# ST_LINK_V2-1.net
KiCad netlist of a schematic drawn in Altium Designer
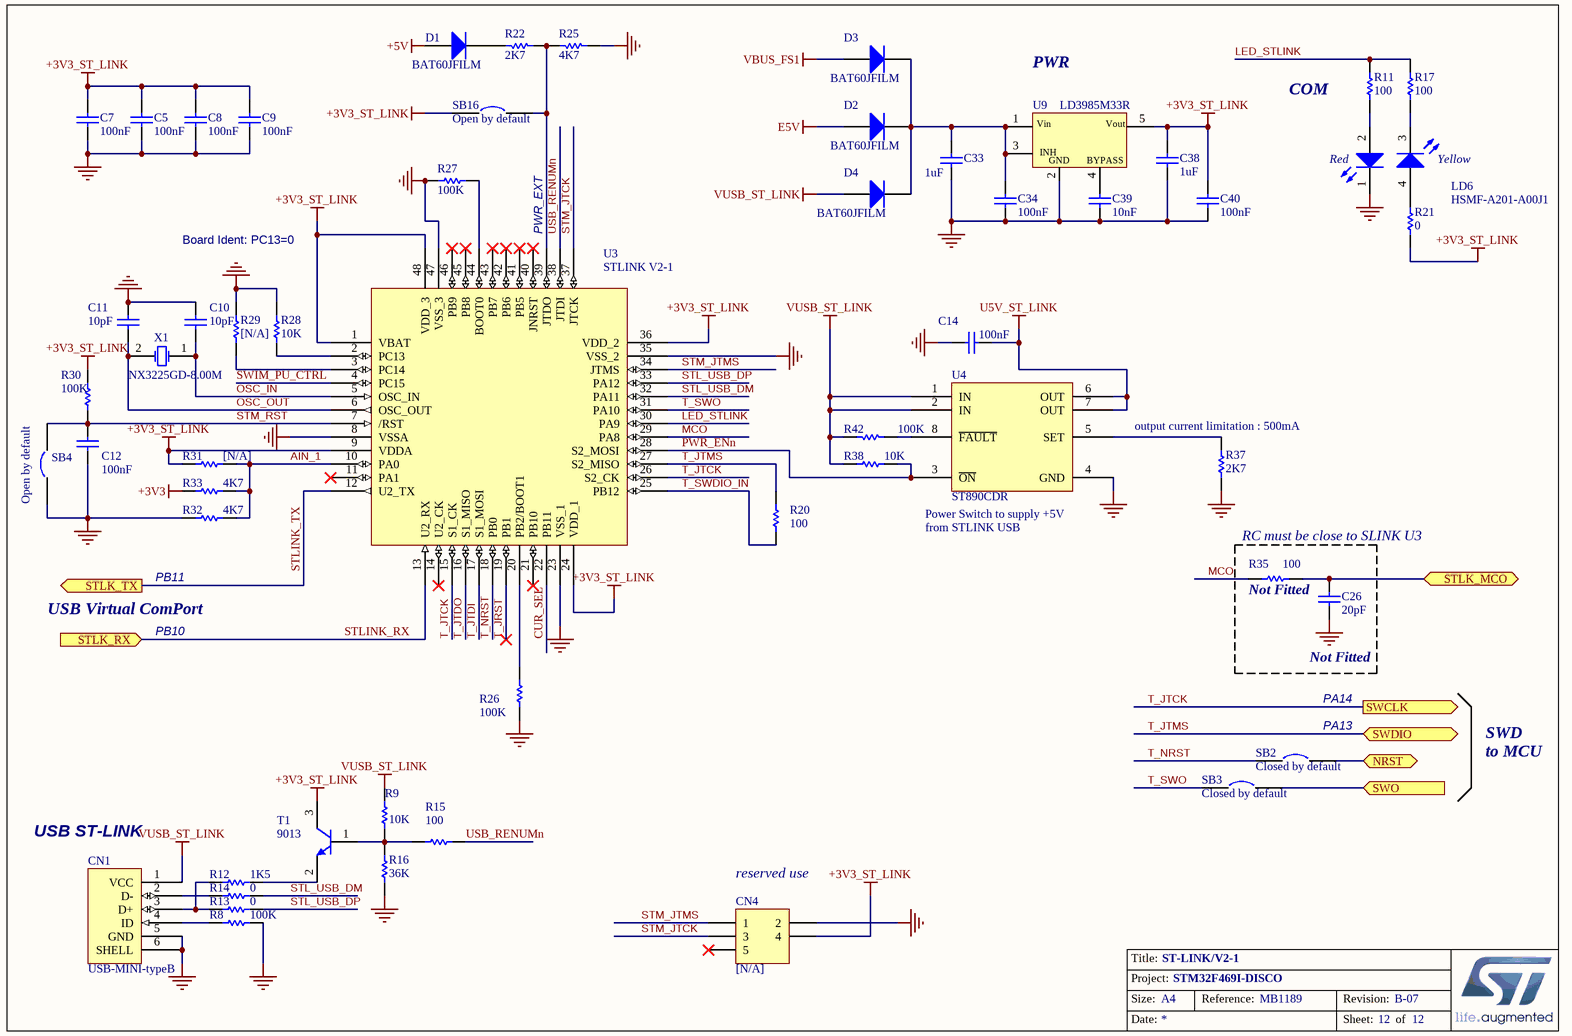
[diagram p0: ST_LINK_V2-1.SCHDOC]

(export (version "E")
  (design (tool "Eeschema 10.0.6"))
  (components
    (comp (ref "C5")
      (value "100nF")
      (footprint "0402C")
      (description "Capacitor 0402 / 0603 / 0805")
      (libsource (lib "MCD_TOOLS") (part "Capacitor_ST"))
    )
    (comp (ref "C7")
      (value "100nF")
      (footprint "0402C")
      (description "Capacitor 0402 / 0603 / 0805")
      (libsource (lib "MCD_TOOLS") (part "Capacitor_ST"))
    )
    (comp (ref "C8")
      (value "100nF")
      (footprint "0402C")
      (description "Capacitor 0402 / 0603 / 0805")
      (libsource (lib "MCD_TOOLS") (part "Capacitor_ST"))
    )
    (comp (ref "C9")
      (value "100nF")
      (footprint "0402C")
      (description "Capacitor 0402 / 0603 / 0805")
      (libsource (lib "MCD_TOOLS") (part "Capacitor_ST"))
    )
    (comp (ref "C10")
      (value "10pF")
      (footprint "0603C")
      (description "Capacitor 0402 / 0603 / 0805")
      (libsource (lib "MCD_TOOLS") (part "Capacitor_ST"))
    )
    (comp (ref "C11")
      (value "10pF")
      (footprint "0603C")
      (description "Capacitor 0402 / 0603 / 0805")
      (libsource (lib "MCD_TOOLS") (part "Capacitor_ST"))
    )
    (comp (ref "C12")
      (value "100nF")
      (footprint "0402C")
      (description "Capacitor 0402 / 0603 / 0805")
      (libsource (lib "MCD_TOOLS") (part "Capacitor_ST"))
    )
    (comp (ref "C14")
      (value "100nF")
      (footprint "0402C")
      (description "Capacitor 0402 / 0603 / 0805")
      (libsource (lib "MCD_TOOLS") (part "Capacitor_ST"))
    )
    (comp (ref "C26")
      (value "20pF")
      (footprint "0603C")
      (description "Capacitor,20pF,50V,NPO,5%,0402,YAGEO")
      (libsource (lib "MCD_TOOLS") (part "Cap_20pF_NPO_5%_0402"))
    )
    (comp (ref "C33")
      (value "1uF")
      (footprint "0603C")
      (description "Capacitor")
      (fields (field (name "TOLERANCE") "10%"))
      (libsource (lib "MB963_1") (part "CAP SMD 0603  X5R 1µF 25V 10%"))
    )
    (comp (ref "C34")
      (value "100nF")
      (footprint "0402C")
      (description "Capacitor 0402 / 0603 / 0805")
      (libsource (lib "MCD_TOOLS") (part "Capacitor_ST"))
    )
    (comp (ref "C38")
      (value "1uF")
      (footprint "0603C")
      (description "Capacitor")
      (fields (field (name "TOLERANCE") "10%"))
      (libsource (lib "MB963_1") (part "CAP SMD 0603  X5R 1µF 25V 10%"))
    )
    (comp (ref "C39")
      (value "10nF")
      (footprint "0603C")
      (description "0603  X7R 10NF")
      (fields (field (name "TOLERANCE") "10%"))
      (libsource (lib "MB963_1") (part "CAP SMD 0603  X7R 10000PF 50V 10%"))
    )
    (comp (ref "C40")
      (value "100nF")
      (footprint "0402C")
      (description "Capacitor 0402 / 0603 / 0805")
      (libsource (lib "MCD_TOOLS") (part "Capacitor_ST"))
    )
    (comp (ref "CN1")
      (value "USB-MINI-typeB")
      (footprint "MINIUSB_AB_5SM_RA")
      (description "USB,MINI-USB-5P/F, 5075BMR-05-M")
      (libsource (lib "MCD_TOOLS") (part "USB-MINI-typeB connector"))
    )
    (comp (ref "CN4")
      (value "[N/A]")
      (footprint "HDR_2X3-1_2R54-6")
      (description "Header, 3-Pin, Dual row")
      (fields (field (name "PUBLISHER") "Altium Limited"))
      (libsource (lib "Miscellaneous Connectors") (part "Header 3X2"))
    )
    (comp (ref "D1")
      (value "BAT60JFILM")
      (footprint "SOD-323")
      (libsource (lib "MCD_TOOLS") (part "BAT60JFILM"))
    )
    (comp (ref "D2")
      (value "BAT60JFILM")
      (footprint "SOD-323")
      (libsource (lib "MCD_TOOLS") (part "BAT60JFILM"))
    )
    (comp (ref "D3")
      (value "BAT60JFILM")
      (footprint "SOD-323")
      (libsource (lib "MCD_TOOLS") (part "BAT60JFILM"))
    )
    (comp (ref "D4")
      (value "BAT60JFILM")
      (footprint "SOD-323")
      (libsource (lib "MCD_TOOLS") (part "BAT60JFILM"))
    )
    (comp (ref "LD6")
      (value "HSMF-A201-A00J1")
      (footprint "LED2_3528")
      (libsource (lib "MB819") (part "HSMF-A201-A00J1"))
    )
    (comp (ref "R8")
      (value "100K")
      (footprint "0603R")
      (description "Resistor")
      (fields (field (name "PUBLISHER") "Altium Limited"))
      (libsource (lib "Miscellaneous Devices") (part "res1"))
    )
    (comp (ref "R9")
      (value "10K")
      (footprint "0402R")
      (description "Resistor")
      (fields (field (name "PUBLISHER") "Altium Limited"))
      (libsource (lib "") (part "Res1_2"))
    )
    (comp (ref "R11")
      (value "100")
      (footprint "0603R")
      (description "Resistor")
      (fields (field (name "PUBLISHER") "Altium Limited"))
      (libsource (lib "") (part "Res1_2"))
    )
    (comp (ref "R12")
      (value "1K5")
      (footprint "0603R")
      (description "Resistor 0402 or 0603 or 0805")
      (libsource (lib "Miscellaneous Devices") (part "Res1"))
    )
    (comp (ref "R13")
      (value "0")
      (footprint "0603R")
      (description "Resistor 0402 or 0603 or 0805")
      (libsource (lib "Miscellaneous Devices") (part "Res1"))
    )
    (comp (ref "R14")
      (value "0")
      (footprint "0603R")
      (description "Resistor 0402 or 0603 or 0805")
      (libsource (lib "Miscellaneous Devices") (part "Res1"))
    )
    (comp (ref "R15")
      (value "100")
      (footprint "0603R")
      (description "Resistor 0402 or 0603 or 0805")
      (libsource (lib "Miscellaneous Devices") (part "Res1"))
    )
    (comp (ref "R16")
      (value "36K")
      (footprint "0603R")
      (description "Resistor")
      (fields (field (name "PUBLISHER") "Altium Limited"))
      (libsource (lib "") (part "Res1_2"))
    )
    (comp (ref "R17")
      (value "100")
      (footprint "0603R")
      (description "Resistor")
      (fields (field (name "PUBLISHER") "Altium Limited"))
      (libsource (lib "") (part "Res1_2"))
    )
    (comp (ref "R20")
      (value "100")
      (footprint "STM-SMEE:0603R")
      (description "Resistor 0402 or 0603 or 0805")
      (libsource (lib "MCD_TOOLS") (part "Resistor_ST"))
    )
    (comp (ref "R21")
      (value "0")
      (footprint "0603R")
      (description "Resistor")
      (fields (field (name "PUBLISHER") "Altium Limited"))
      (libsource (lib "") (part "Res1_2"))
    )
    (comp (ref "R22")
      (value "2K7")
      (footprint "0603R")
      (description "Resistor")
      (fields (field (name "PUBLISHER") "Altium Limited"))
      (libsource (lib "") (part "Res1_1"))
    )
    (comp (ref "R25")
      (value "4K7")
      (footprint "0603R")
      (description "Resistor")
      (fields (field (name "PUBLISHER") "Altium Limited"))
      (libsource (lib "") (part "Res1_1"))
    )
    (comp (ref "R26")
      (value "100K")
      (footprint "0603R")
      (description "Resistor 0402 or 0603 or 0805")
      (libsource (lib "Miscellaneous Devices") (part "Res1"))
    )
    (comp (ref "R27")
      (value "100K")
      (footprint "0603R")
      (description "Resistor 0402 or 0603 or 0805")
      (libsource (lib "Miscellaneous Devices") (part "Res1"))
    )
    (comp (ref "R28")
      (value "10K")
      (footprint "0402R")
      (description "Resistor 0402 or 0603 or 0805")
      (libsource (lib "Miscellaneous Devices") (part "Res1"))
    )
    (comp (ref "R29")
      (value "[N/A]")
      (footprint "0603R")
      (description "Resistor 0402 or 0603 or 0805")
      (libsource (lib "Miscellaneous Devices") (part "Res1"))
    )
    (comp (ref "R30")
      (value "100K")
      (footprint "0603R")
      (description "Resistor 0402 or 0603 or 0805")
      (libsource (lib "Miscellaneous Devices") (part "Res1"))
    )
    (comp (ref "R31")
      (value "[N/A]")
      (footprint "0603R")
      (description "Resistor 0402 or 0603 or 0805")
      (libsource (lib "Miscellaneous Devices") (part "Res1"))
    )
    (comp (ref "R32")
      (value "4K7")
      (footprint "0603R")
      (description "Resistor 0402 or 0603 or 0805")
      (libsource (lib "Miscellaneous Devices") (part "Res1"))
    )
    (comp (ref "R33")
      (value "4K7")
      (footprint "0603R")
      (description "Resistor 0402 or 0603 or 0805")
      (libsource (lib "Miscellaneous Devices") (part "Res1"))
    )
    (comp (ref "R35")
      (value "100")
      (footprint "0603R")
      (description "Resistor 0402 or 0603 or 0805")
      (libsource (lib "Miscellaneous Devices") (part "Res1"))
    )
    (comp (ref "R37")
      (value "2K7")
      (footprint "STM-SMEE:0603R")
      (description "Resistor 0402 or 0603 or 0805")
      (libsource (lib "MCD_TOOLS") (part "Resistor_ST"))
    )
    (comp (ref "R38")
      (value "10K")
      (footprint "0402R")
      (description "Resistor 0402 or 0603 or 0805")
      (libsource (lib "MCD_TOOLS") (part "Resistor_ST"))
    )
    (comp (ref "R42")
      (value "100K")
      (footprint "0603R")
      (description "Resistor")
      (fields (field (name "PUBLISHER") "Altium Limited"))
      (libsource (lib "*") (part "Res1"))
    )
    (comp (ref "SB2")
      (value "Closed by default")
      (footprint "SB_0603")
      (description "Circuit Breaker")
      (fields (field (name "PUBLISHER") "Altium Limited"))
      (libsource (lib "Miscellaneous Devices") (part "Circuit Breaker"))
    )
    (comp (ref "SB3")
      (value "Closed by default")
      (footprint "SB_0603")
      (description "Circuit Breaker")
      (fields (field (name "PUBLISHER") "Altium Limited"))
      (libsource (lib "Miscellaneous Devices") (part "Circuit Breaker"))
    )
    (comp (ref "SB4")
      (value "Open by default")
      (footprint "SB_0603")
      (description "Circuit Breaker")
      (fields (field (name "PUBLISHER") "Altium Limited"))
      (libsource (lib "Miscellaneous Devices") (part "Circuit Breaker"))
    )
    (comp (ref "SB16")
      (value "Open by default")
      (footprint "SB_0603")
      (description "Circuit Breaker")
      (fields (field (name "PUBLISHER") "Altium Limited"))
      (libsource (lib "Miscellaneous Devices") (part "Circuit Breaker"))
    )
    (comp (ref "T1")
      (value "9013")
      (footprint "SOT-23")
      (description "NPN Bipolar Transistor")
      (fields (field (name "PUBLISHER") "Altium Limited"))
      (libsource (lib "MB1167") (part "NPN"))
    )
    (comp (ref "U3")
      (value "STLINK V2-1")
      (footprint "LQFP48_0R5_9X9")
      (libsource (lib "*") (part "STM32F10x(48pin)"))
    )
    (comp (ref "U4")
      (value "ST890CDR")
      (footprint "SOIC8_1R27_4R9X6")
      (libsource (lib "MB1167") (part "ST890CDR"))
    )
    (comp (ref "U9")
      (value "LD3985M33R")
      (footprint "SOT23-5")
      (description "Ultra low drop-low noise BiCMOS voltage, regulators low ESR capacitors compatible")
      (libsource (lib "MCD_TOOLS") (part "LD3985M33R"))
    )
    (comp (ref "X1")
      (value "NX3225GD-8.00M")
      (footprint "XTAL_2SM_3R2X2R5_H1")
      (description "Crystal 8Mhz, 8pF, -+50PPM, SMD")
      (libsource (lib "MCD_TOOLS") (part "XTAL_8M_NX3225GD"))
    )
  )
  (nets
    (net (code "1") (name "+3V3") (class "Default")
      (node (ref "R33") (pin "1") (pinfunction "1_1") (pintype "passive"))
    )
    (net (code "2") (name "+3V3_ST_LINK") (class "Default")
      (node (ref "C38") (pin "1") (pinfunction "1_1") (pintype "passive"))
      (node (ref "C40") (pin "2") (pinfunction "2_2") (pintype "passive"))
      (node (ref "C5") (pin "2") (pinfunction "2_2") (pintype "passive"))
      (node (ref "C7") (pin "2") (pinfunction "2_2") (pintype "passive"))
      (node (ref "C8") (pin "2") (pinfunction "2_2") (pintype "passive"))
      (node (ref "C9") (pin "2") (pinfunction "2_2") (pintype "passive"))
      (node (ref "CN4") (pin "4") (pinfunction "4_4") (pintype "passive"))
      (node (ref "R21") (pin "2") (pinfunction "2_2") (pintype "passive"))
      (node (ref "R30") (pin "2") (pinfunction "2_2") (pintype "passive"))
      (node (ref "R31") (pin "1") (pinfunction "1_1") (pintype "passive"))
      (node (ref "SB16") (pin "1") (pinfunction "1_1") (pintype "passive"))
      (node (ref "T1") (pin "3") (pinfunction "C_3") (pintype "passive"))
      (node (ref "U3") (pin "1") (pinfunction "VBAT_1") (pintype "power_in"))
      (node (ref "U3") (pin "24") (pinfunction "VDD_1_24") (pintype "power_in"))
      (node (ref "U3") (pin "36") (pinfunction "VDD_2_36") (pintype "power_in"))
      (node (ref "U3") (pin "48") (pinfunction "VDD_3_48") (pintype "power_in"))
      (node (ref "U3") (pin "9") (pinfunction "VDDA_9") (pintype "power_in"))
      (node (ref "U9") (pin "5") (pinfunction "Vout_5") (pintype "passive"))
    )
    (net (code "3") (name "+5V") (class "Default")
      (node (ref "D1") (pin "1") (pinfunction "A_1") (pintype "passive"))
    )
    (net (code "4") (name "/AIN_1") (class "Default")
      (node (ref "R31") (pin "2") (pinfunction "2_2") (pintype "passive"))
      (node (ref "R32") (pin "2") (pinfunction "2_2") (pintype "passive"))
      (node (ref "R33") (pin "2") (pinfunction "2_2") (pintype "passive"))
      (node (ref "U3") (pin "10") (pinfunction "PA0_10") (pintype "bidirectional"))
    )
    (net (code "5") (name "/CUR_SEL") (class "Default")
      (node (ref "U3") (pin "22") (pinfunction "PB11_22") (pintype "passive"))
    )
    (net (code "6") (name "/LED_STLINK") (class "Default")
      (node (ref "R11") (pin "1") (pinfunction "1_1") (pintype "passive"))
      (node (ref "R17") (pin "1") (pinfunction "1_1") (pintype "passive"))
      (node (ref "U3") (pin "30") (pinfunction "PA9_30") (pintype "bidirectional"))
    )
    (net (code "7") (name "/MCO") (class "Default")
      (node (ref "R35") (pin "1") (pinfunction "1_1") (pintype "passive"))
      (node (ref "U3") (pin "29") (pinfunction "PA8_29") (pintype "bidirectional"))
    )
    (net (code "8") (name "/NRST") (class "Default")
      (node (ref "SB2") (pin "2") (pinfunction "2_2") (pintype "passive"))
    )
    (net (code "9") (name "/OSC_IN") (class "Default")
      (node (ref "C10") (pin "1") (pinfunction "1_1") (pintype "passive"))
      (node (ref "U3") (pin "5") (pinfunction "OSC_IN_5") (pintype "input"))
      (node (ref "X1") (pin "1") (pinfunction "OSC1_1") (pintype "passive"))
    )
    (net (code "10") (name "/OSC_OUT") (class "Default")
      (node (ref "C11") (pin "1") (pinfunction "1_1") (pintype "passive"))
      (node (ref "U3") (pin "6") (pinfunction "OSC_OUT_6") (pintype "output"))
      (node (ref "X1") (pin "2") (pinfunction "OSC2_2") (pintype "passive"))
    )
    (net (code "11") (name "/PWR_ENn") (class "Default")
      (node (ref "R38") (pin "2") (pinfunction "2_2") (pintype "passive"))
      (node (ref "U3") (pin "28") (pinfunction "S2_MOSI_28") (pintype "bidirectional"))
      (node (ref "U4") (pin "3") (pinfunction "~{ON}_3") (pintype "passive"))
    )
    (net (code "12") (name "/STLINK_RX") (class "Default")
      (node (ref "U3") (pin "13") (pinfunction "U2_RX_13") (pintype "input"))
    )
    (net (code "13") (name "/STLINK_TX") (class "Default")
      (node (ref "U3") (pin "12") (pinfunction "U2_TX_12") (pintype "output"))
    )
    (net (code "14") (name "/STLK_MCO") (class "Default")
      (node (ref "C26") (pin "1") (pinfunction "1_1") (pintype "passive"))
      (node (ref "R35") (pin "2") (pinfunction "2_2") (pintype "passive"))
    )
    (net (code "15") (name "/STL_USB_DM") (class "Default")
      (node (ref "R14") (pin "2") (pinfunction "2_2") (pintype "passive"))
      (node (ref "U3") (pin "32") (pinfunction "PA11_32") (pintype "bidirectional"))
    )
    (net (code "16") (name "/STL_USB_DP") (class "Default")
      (node (ref "R13") (pin "2") (pinfunction "2_2") (pintype "passive"))
      (node (ref "U3") (pin "33") (pinfunction "PA12_33") (pintype "bidirectional"))
    )
    (net (code "17") (name "/STM_JTCK") (class "Default")
      (node (ref "CN4") (pin "3") (pinfunction "3_3") (pintype "passive"))
      (node (ref "U3") (pin "37") (pinfunction "JTCK_37") (pintype "bidirectional"))
    )
    (net (code "18") (name "/STM_JTMS") (class "Default")
      (node (ref "CN4") (pin "1") (pinfunction "1_1") (pintype "passive"))
      (node (ref "U3") (pin "34") (pinfunction "JTMS_34") (pintype "bidirectional"))
    )
    (net (code "19") (name "/STM_RST") (class "Default")
      (node (ref "C12") (pin "2") (pinfunction "2_2") (pintype "passive"))
      (node (ref "R30") (pin "1") (pinfunction "1_1") (pintype "passive"))
      (node (ref "SB4") (pin "2") (pinfunction "2_2") (pintype "passive"))
      (node (ref "U3") (pin "7") (pinfunction "/RST_7") (pintype "input"))
    )
    (net (code "20") (name "/SWIM_PU_CTRL") (class "Default")
      (node (ref "U3") (pin "4") (pinfunction "PC15_4") (pintype "bidirectional"))
    )
    (net (code "21") (name "/SWO") (class "Default")
      (node (ref "SB3") (pin "2") (pinfunction "2_2") (pintype "passive"))
    )
    (net (code "22") (name "/T_JRST") (class "Default")
      (node (ref "U3") (pin "19") (pinfunction "PB1_19") (pintype "bidirectional+no_connect"))
    )
    (net (code "23") (name "/T_JTCK") (class "Default")
      (node (ref "U3") (pin "15") (pinfunction "S1_CK_15") (pintype "bidirectional"))
      (node (ref "U3") (pin "26") (pinfunction "S2_CK_26") (pintype "bidirectional"))
    )
    (net (code "24") (name "/T_JTDI") (class "Default")
      (node (ref "U3") (pin "17") (pinfunction "S1_MOSI_17") (pintype "bidirectional"))
    )
    (net (code "25") (name "/T_JTDO") (class "Default")
      (node (ref "U3") (pin "16") (pinfunction "S1_MISO_16") (pintype "bidirectional"))
    )
    (net (code "26") (name "/T_JTMS") (class "Default")
      (node (ref "R20") (pin "2") (pinfunction "2_2") (pintype "passive"))
      (node (ref "U3") (pin "27") (pinfunction "S2_MISO_27") (pintype "bidirectional"))
    )
    (net (code "27") (name "/T_NRST") (class "Default")
      (node (ref "SB2") (pin "1") (pinfunction "1_1") (pintype "passive"))
      (node (ref "U3") (pin "18") (pinfunction "PB0_18") (pintype "bidirectional"))
    )
    (net (code "28") (name "/T_SWDIO_IN") (class "Default")
      (node (ref "R20") (pin "1") (pinfunction "1_1") (pintype "passive"))
      (node (ref "U3") (pin "25") (pinfunction "PB12_25") (pintype "bidirectional"))
    )
    (net (code "29") (name "/T_SWO") (class "Default")
      (node (ref "SB3") (pin "1") (pinfunction "1_1") (pintype "passive"))
      (node (ref "U3") (pin "31") (pinfunction "PA10_31") (pintype "bidirectional"))
    )
    (net (code "30") (name "/USB_RENUMn") (class "Default")
      (node (ref "R15") (pin "2") (pinfunction "2_2") (pintype "passive"))
      (node (ref "U3") (pin "38") (pinfunction "JTDI_38") (pintype "bidirectional"))
    )
    (net (code "31") (name "E5V") (class "Default")
      (node (ref "D2") (pin "1") (pinfunction "A_1") (pintype "passive"))
    )
    (net (code "32") (name "GND") (class "Default")
      (node (ref "C10") (pin "2") (pinfunction "2_2") (pintype "passive"))
      (node (ref "C11") (pin "2") (pinfunction "2_2") (pintype "passive"))
      (node (ref "C12") (pin "1") (pinfunction "1_1") (pintype "passive"))
      (node (ref "C14") (pin "1") (pinfunction "1_1") (pintype "passive"))
      (node (ref "C26") (pin "2") (pinfunction "2_2") (pintype "passive"))
      (node (ref "C33") (pin "1") (pinfunction "1_1") (pintype "passive"))
      (node (ref "C34") (pin "1") (pinfunction "1_1") (pintype "passive"))
      (node (ref "C38") (pin "2") (pinfunction "2_2") (pintype "passive"))
      (node (ref "C39") (pin "1") (pinfunction "1_1") (pintype "passive"))
      (node (ref "C40") (pin "1") (pinfunction "1_1") (pintype "passive"))
      (node (ref "C5") (pin "1") (pinfunction "1_1") (pintype "passive"))
      (node (ref "C7") (pin "1") (pinfunction "1_1") (pintype "passive"))
      (node (ref "C8") (pin "1") (pinfunction "1_1") (pintype "passive"))
      (node (ref "C9") (pin "1") (pinfunction "1_1") (pintype "passive"))
      (node (ref "CN1") (pin "5") (pinfunction "GND_5") (pintype "passive"))
      (node (ref "CN1") (pin "6") (pinfunction "SHELL_6") (pintype "passive"))
      (node (ref "CN4") (pin "2") (pinfunction "2_2") (pintype "passive"))
      (node (ref "LD6") (pin "1") (pinfunction "RED_cathode_1") (pintype "passive"))
      (node (ref "R16") (pin "1") (pinfunction "1_1") (pintype "passive"))
      (node (ref "R25") (pin "2") (pinfunction "2_2") (pintype "passive"))
      (node (ref "R26") (pin "1") (pinfunction "1_1") (pintype "passive"))
      (node (ref "R27") (pin "1") (pinfunction "1_1") (pintype "passive"))
      (node (ref "R28") (pin "1") (pinfunction "1_1") (pintype "passive"))
      (node (ref "R29") (pin "1") (pinfunction "1_1") (pintype "passive"))
      (node (ref "R32") (pin "1") (pinfunction "1_1") (pintype "passive"))
      (node (ref "R37") (pin "2") (pinfunction "2_2") (pintype "passive"))
      (node (ref "R8") (pin "2") (pinfunction "2_2") (pintype "passive"))
      (node (ref "SB4") (pin "1") (pinfunction "1_1") (pintype "passive"))
      (node (ref "U3") (pin "23") (pinfunction "VSS_1_23") (pintype "passive"))
      (node (ref "U3") (pin "35") (pinfunction "VSS_2_35") (pintype "passive"))
      (node (ref "U3") (pin "47") (pinfunction "VSS_3_47") (pintype "passive"))
      (node (ref "U3") (pin "8") (pinfunction "VSSA_8") (pintype "passive"))
      (node (ref "U4") (pin "4") (pinfunction "GND_4") (pintype "passive"))
      (node (ref "U9") (pin "2") (pinfunction "GND_2") (pintype "passive"))
    )
    (net (code "33") (name "Net-(CN1-D+)") (class "Default")
      (node (ref "CN1") (pin "3") (pinfunction "D+_3") (pintype "bidirectional"))
      (node (ref "R12") (pin "1") (pinfunction "1_1") (pintype "passive"))
      (node (ref "R13") (pin "1") (pinfunction "1_1") (pintype "passive"))
    )
    (net (code "34") (name "Net-(CN1-D-)") (class "Default")
      (node (ref "CN1") (pin "2") (pinfunction "D-_2") (pintype "bidirectional"))
      (node (ref "R14") (pin "1") (pinfunction "1_1") (pintype "passive"))
    )
    (net (code "35") (name "Net-(CN1-ID)") (class "Default")
      (node (ref "CN1") (pin "4") (pinfunction "ID_4") (pintype "input"))
      (node (ref "R8") (pin "1") (pinfunction "1_1") (pintype "passive"))
    )
    (net (code "36") (name "Net-(D1-K)") (class "Default")
      (node (ref "D1") (pin "2") (pinfunction "K_2") (pintype "passive"))
      (node (ref "R22") (pin "1") (pinfunction "1_1") (pintype "passive"))
    )
    (net (code "37") (name "Net-(D2-K)") (class "Default")
      (node (ref "C33") (pin "2") (pinfunction "2_2") (pintype "passive"))
      (node (ref "C34") (pin "2") (pinfunction "2_2") (pintype "passive"))
      (node (ref "D2") (pin "2") (pinfunction "K_2") (pintype "passive"))
      (node (ref "D3") (pin "2") (pinfunction "K_2") (pintype "passive"))
      (node (ref "D4") (pin "2") (pinfunction "K_2") (pintype "passive"))
      (node (ref "U9") (pin "1") (pinfunction "Vin_1") (pintype "passive"))
      (node (ref "U9") (pin "3") (pinfunction "CE_3") (pintype "passive"))
    )
    (net (code "38") (name "Net-(LD6-Red_anode)") (class "Default")
      (node (ref "LD6") (pin "2") (pinfunction "Red_anode_2") (pintype "passive"))
      (node (ref "R11") (pin "2") (pinfunction "2_2") (pintype "passive"))
    )
    (net (code "39") (name "Net-(LD6-YellowGreen_anode)") (class "Default")
      (node (ref "LD6") (pin "4") (pinfunction "YellowGreen_anode_4") (pintype "passive"))
      (node (ref "R21") (pin "1") (pinfunction "1_1") (pintype "passive"))
    )
    (net (code "40") (name "Net-(LD6-YellowGreen_cathode)") (class "Default")
      (node (ref "LD6") (pin "3") (pinfunction "YellowGreen_cathode_3") (pintype "passive"))
      (node (ref "R17") (pin "2") (pinfunction "2_2") (pintype "passive"))
    )
    (net (code "41") (name "Net-(T1-B)") (class "Default")
      (node (ref "R15") (pin "1") (pinfunction "1_1") (pintype "passive"))
      (node (ref "R16") (pin "2") (pinfunction "2_2") (pintype "passive"))
      (node (ref "R9") (pin "1") (pinfunction "1_1") (pintype "passive"))
      (node (ref "T1") (pin "1") (pinfunction "B_1") (pintype "passive"))
    )
    (net (code "42") (name "Net-(T1-E)") (class "Default")
      (node (ref "R12") (pin "2") (pinfunction "2_2") (pintype "passive"))
      (node (ref "T1") (pin "2") (pinfunction "E_2") (pintype "passive"))
    )
    (net (code "43") (name "Net-(U3-BOOT0)") (class "Default")
      (node (ref "R27") (pin "2") (pinfunction "2_2") (pintype "passive"))
      (node (ref "U3") (pin "44") (pinfunction "BOOT0_44") (pintype "bidirectional"))
    )
    (net (code "44") (name "Net-(U3-JTDO)") (class "Default")
      (node (ref "R22") (pin "2") (pinfunction "2_2") (pintype "passive"))
      (node (ref "R25") (pin "1") (pinfunction "1_1") (pintype "passive"))
      (node (ref "SB16") (pin "2") (pinfunction "2_2") (pintype "passive"))
      (node (ref "U3") (pin "39") (pinfunction "JTDO_39") (pintype "bidirectional"))
    )
    (net (code "45") (name "Net-(U3-PB2{slash}BOOT1)") (class "Default")
      (node (ref "R26") (pin "2") (pinfunction "2_2") (pintype "passive"))
      (node (ref "U3") (pin "20") (pinfunction "PB2/BOOT1_20") (pintype "passive"))
    )
    (net (code "46") (name "Net-(U3-PC13)") (class "Default")
      (node (ref "R28") (pin "2") (pinfunction "2_2") (pintype "passive"))
      (node (ref "U3") (pin "2") (pinfunction "PC13_2") (pintype "bidirectional"))
    )
    (net (code "47") (name "Net-(U3-PC14)") (class "Default")
      (node (ref "R29") (pin "2") (pinfunction "2_2") (pintype "passive"))
      (node (ref "U3") (pin "3") (pinfunction "PC14_3") (pintype "bidirectional"))
    )
    (net (code "48") (name "Net-(U4-SET)") (class "Default")
      (node (ref "R37") (pin "1") (pinfunction "1_1") (pintype "passive"))
      (node (ref "U4") (pin "5") (pinfunction "SET_5") (pintype "passive"))
    )
    (net (code "49") (name "Net-(U4-~{FAULT})") (class "Default")
      (node (ref "R42") (pin "2") (pinfunction "2_2") (pintype "passive"))
      (node (ref "U4") (pin "8") (pinfunction "~{FAULT}_8") (pintype "passive"))
    )
    (net (code "50") (name "Net-(U9-BYPASS)") (class "Default")
      (node (ref "C39") (pin "2") (pinfunction "2_2") (pintype "passive"))
      (node (ref "U9") (pin "4") (pinfunction "BYPASS_4") (pintype "passive"))
    )
    (net (code "51") (name "U5V_ST_LINK") (class "Default")
      (node (ref "C14") (pin "2") (pinfunction "2_2") (pintype "passive"))
      (node (ref "U4") (pin "6") (pinfunction "OUT_6") (pintype "passive"))
      (node (ref "U4") (pin "7") (pinfunction "OUT_7") (pintype "passive"))
    )
    (net (code "52") (name "VBUS_FS1") (class "Default")
      (node (ref "D3") (pin "1") (pinfunction "A_1") (pintype "passive"))
    )
    (net (code "53") (name "VUSB_ST_LINK") (class "Default")
      (node (ref "CN1") (pin "1") (pinfunction "VCC_1") (pintype "power_in"))
      (node (ref "D4") (pin "1") (pinfunction "A_1") (pintype "passive"))
      (node (ref "R38") (pin "1") (pinfunction "1_1") (pintype "passive"))
      (node (ref "R42") (pin "1") (pinfunction "1_1") (pintype "passive"))
      (node (ref "R9") (pin "2") (pinfunction "2_2") (pintype "passive"))
      (node (ref "U4") (pin "1") (pinfunction "IN_1") (pintype "passive"))
      (node (ref "U4") (pin "2") (pinfunction "IN_2") (pintype "passive"))
    )
    (net (code "54") (name "unconnected-(CN4-Pad5)") (class "Default")
      (node (ref "CN4") (pin "5") (pinfunction "5_5") (pintype "passive+no_connect"))
    )
    (net (code "55") (name "unconnected-(U3-JNRST-Pad40)") (class "Default")
      (node (ref "U3") (pin "40") (pinfunction "JNRST_40") (pintype "bidirectional+no_connect"))
    )
    (net (code "56") (name "unconnected-(U3-PA1-Pad11)") (class "Default")
      (node (ref "U3") (pin "11") (pinfunction "PA1_11") (pintype "bidirectional+no_connect"))
    )
    (net (code "57") (name "unconnected-(U3-PB5-Pad41)") (class "Default")
      (node (ref "U3") (pin "41") (pinfunction "PB5_41") (pintype "bidirectional+no_connect"))
    )
    (net (code "58") (name "unconnected-(U3-PB6-Pad42)") (class "Default")
      (node (ref "U3") (pin "42") (pinfunction "PB6_42") (pintype "bidirectional+no_connect"))
    )
    (net (code "59") (name "unconnected-(U3-PB7-Pad43)") (class "Default")
      (node (ref "U3") (pin "43") (pinfunction "PB7_43") (pintype "bidirectional+no_connect"))
    )
    (net (code "60") (name "unconnected-(U3-PB8-Pad45)") (class "Default")
      (node (ref "U3") (pin "45") (pinfunction "PB8_45") (pintype "bidirectional+no_connect"))
    )
    (net (code "61") (name "unconnected-(U3-PB9-Pad46)") (class "Default")
      (node (ref "U3") (pin "46") (pinfunction "PB9_46") (pintype "bidirectional+no_connect"))
    )
    (net (code "62") (name "unconnected-(U3-PB10-Pad21)") (class "Default")
      (node (ref "U3") (pin "21") (pinfunction "PB10_21") (pintype "bidirectional+no_connect"))
    )
    (net (code "63") (name "unconnected-(U3-U2_CK-Pad14)") (class "Default")
      (node (ref "U3") (pin "14") (pinfunction "U2_CK_14") (pintype "bidirectional+no_connect"))
    )
  )
)
